# TeamI_PDSfinal.net
KiCad netlist of a schematic drawn in EAGLE
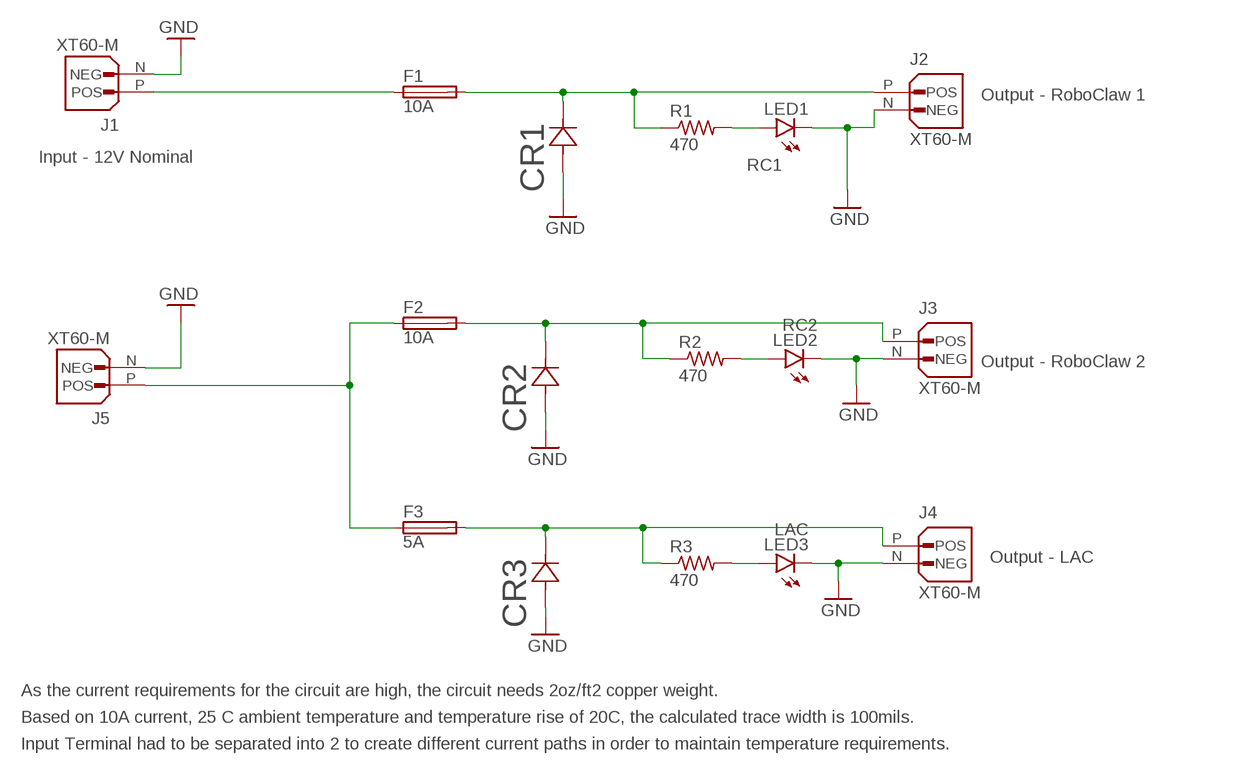
[diagram p0: schematic, sheet 1]

(export (version "E")
  (design (tool "Eeschema 10.0.6"))
  (components
    (comp (ref "CR1")
      (value "P4SMA16A")
      (footprint "eagle-import:P4SMASERIES_LTF")
      (fields (field (name "COPYRIGHT") "Copyright (C) 2025 Ultra Librarian. All rights reserved."))
      (libsource (lib "eagle-import") (part "P4SMA16A"))
    )
    (comp (ref "CR2")
      (value "P4SMA16A")
      (footprint "eagle-import:P4SMASERIES_LTF")
      (fields (field (name "COPYRIGHT") "Copyright (C) 2025 Ultra Librarian. All rights reserved."))
      (libsource (lib "eagle-import") (part "P4SMA16A"))
    )
    (comp (ref "CR3")
      (value "P4SMA16A")
      (footprint "eagle-import:P4SMASERIES_LTF")
      (fields (field (name "COPYRIGHT") "Copyright (C) 2025 Ultra Librarian. All rights reserved."))
      (libsource (lib "eagle-import") (part "P4SMA16A"))
    )
    (comp (ref "F1")
      (value "10A")
      (footprint "eagle-import:TR5")
      (libsource (lib "eagle-import") (part "TR5"))
    )
    (comp (ref "F2")
      (value "10A")
      (footprint "eagle-import:TR5")
      (libsource (lib "eagle-import") (part "TR5"))
    )
    (comp (ref "F3")
      (value "5A")
      (footprint "eagle-import:TE5")
      (libsource (lib "eagle-import") (part "TE5"))
    )
    (comp (ref "J1")
      (value "XT60-M")
      (footprint "eagle-import:AMASS_XT60-M")
      (fields (field (name "MF") "AMASS"))
      (libsource (lib "eagle-import") (part "XT60-M"))
    )
    (comp (ref "J2")
      (value "XT60-M")
      (footprint "eagle-import:AMASS_XT60-M")
      (fields (field (name "MF") "AMASS"))
      (libsource (lib "eagle-import") (part "XT60-M"))
    )
    (comp (ref "J3")
      (value "XT60-M")
      (footprint "eagle-import:AMASS_XT60-M")
      (fields (field (name "MF") "AMASS"))
      (libsource (lib "eagle-import") (part "XT60-M"))
    )
    (comp (ref "J4")
      (value "XT60-M")
      (footprint "eagle-import:AMASS_XT60-M")
      (fields (field (name "MF") "AMASS"))
      (libsource (lib "eagle-import") (part "XT60-M"))
    )
    (comp (ref "J5")
      (value "XT60-M")
      (footprint "eagle-import:AMASS_XT60-M")
      (fields (field (name "MF") "AMASS"))
      (libsource (lib "eagle-import") (part "XT60-M"))
    )
    (comp (ref "LED1")
      (value "RC1")
      (footprint "eagle-import:1206")
      (libsource (lib "eagle-import") (part "LEDSMT1206"))
    )
    (comp (ref "LED2")
      (value "RC2")
      (footprint "eagle-import:1206")
      (libsource (lib "eagle-import") (part "LEDSMT1206"))
    )
    (comp (ref "LED3")
      (value "LAC")
      (footprint "eagle-import:1206")
      (libsource (lib "eagle-import") (part "LEDSMT1206"))
    )
    (comp (ref "R1")
      (value "470")
      (footprint "eagle-import:R1206")
      (libsource (lib "eagle-import") (part "R-US_R1206"))
    )
    (comp (ref "R2")
      (value "470")
      (footprint "eagle-import:R1206")
      (libsource (lib "eagle-import") (part "R-US_R1206"))
    )
    (comp (ref "R3")
      (value "470")
      (footprint "eagle-import:R1206")
      (libsource (lib "eagle-import") (part "R-US_R1206"))
    )
  )
  (nets
    (net (code "1") (name "GND") (class "Default")
      (node (ref "CR1") (pin "2") (pinfunction "2_2") (pintype "passive"))
      (node (ref "CR2") (pin "2") (pinfunction "2_2") (pintype "passive"))
      (node (ref "CR3") (pin "2") (pinfunction "2_2") (pintype "passive"))
      (node (ref "J1") (pin "N") (pinfunction "NEG_N") (pintype "passive"))
      (node (ref "J2") (pin "N") (pinfunction "NEG_N") (pintype "passive"))
      (node (ref "J3") (pin "N") (pinfunction "NEG_N") (pintype "passive"))
      (node (ref "J4") (pin "N") (pinfunction "NEG_N") (pintype "passive"))
      (node (ref "J5") (pin "N") (pinfunction "NEG_N") (pintype "passive"))
      (node (ref "LED1") (pin "C") (pinfunction "C_C") (pintype "passive"))
      (node (ref "LED2") (pin "C") (pinfunction "C_C") (pintype "passive"))
      (node (ref "LED3") (pin "C") (pinfunction "C_C") (pintype "passive"))
    )
    (net (code "2") (name "Net-(J1-POS)") (class "Default")
      (node (ref "F1") (pin "1") (pinfunction "1_1") (pintype "passive"))
      (node (ref "J1") (pin "P") (pinfunction "POS_P") (pintype "passive"))
    )
    (net (code "3") (name "Net-(J2-POS)") (class "Default")
      (node (ref "CR1") (pin "1") (pinfunction "1_1") (pintype "passive"))
      (node (ref "F1") (pin "2") (pinfunction "2_2") (pintype "passive"))
      (node (ref "J2") (pin "P") (pinfunction "POS_P") (pintype "passive"))
      (node (ref "R1") (pin "1") (pinfunction "1_1") (pintype "passive"))
    )
    (net (code "4") (name "Net-(J3-POS)") (class "Default")
      (node (ref "CR2") (pin "1") (pinfunction "1_1") (pintype "passive"))
      (node (ref "F2") (pin "2") (pinfunction "2_2") (pintype "passive"))
      (node (ref "J3") (pin "P") (pinfunction "POS_P") (pintype "passive"))
      (node (ref "R2") (pin "1") (pinfunction "1_1") (pintype "passive"))
    )
    (net (code "5") (name "Net-(J4-POS)") (class "Default")
      (node (ref "CR3") (pin "1") (pinfunction "1_1") (pintype "passive"))
      (node (ref "F3") (pin "2") (pinfunction "2_2") (pintype "passive"))
      (node (ref "J4") (pin "P") (pinfunction "POS_P") (pintype "passive"))
      (node (ref "R3") (pin "1") (pinfunction "1_1") (pintype "passive"))
    )
    (net (code "6") (name "Net-(J5-POS)") (class "Default")
      (node (ref "F2") (pin "1") (pinfunction "1_1") (pintype "passive"))
      (node (ref "F3") (pin "1") (pinfunction "1_1") (pintype "passive"))
      (node (ref "J5") (pin "P") (pinfunction "POS_P") (pintype "passive"))
    )
    (net (code "7") (name "Net-(LED1-PadA)") (class "Default")
      (node (ref "LED1") (pin "A") (pinfunction "A_A") (pintype "passive"))
      (node (ref "R1") (pin "2") (pinfunction "2_2") (pintype "passive"))
    )
    (net (code "8") (name "Net-(LED2-PadA)") (class "Default")
      (node (ref "LED2") (pin "A") (pinfunction "A_A") (pintype "passive"))
      (node (ref "R2") (pin "2") (pinfunction "2_2") (pintype "passive"))
    )
    (net (code "9") (name "Net-(LED3-PadA)") (class "Default")
      (node (ref "LED3") (pin "A") (pinfunction "A_A") (pintype "passive"))
      (node (ref "R3") (pin "2") (pinfunction "2_2") (pintype "passive"))
    )
  )
)
